# DK_POWER.net
KiCad netlist of a schematic drawn in Altium Designer
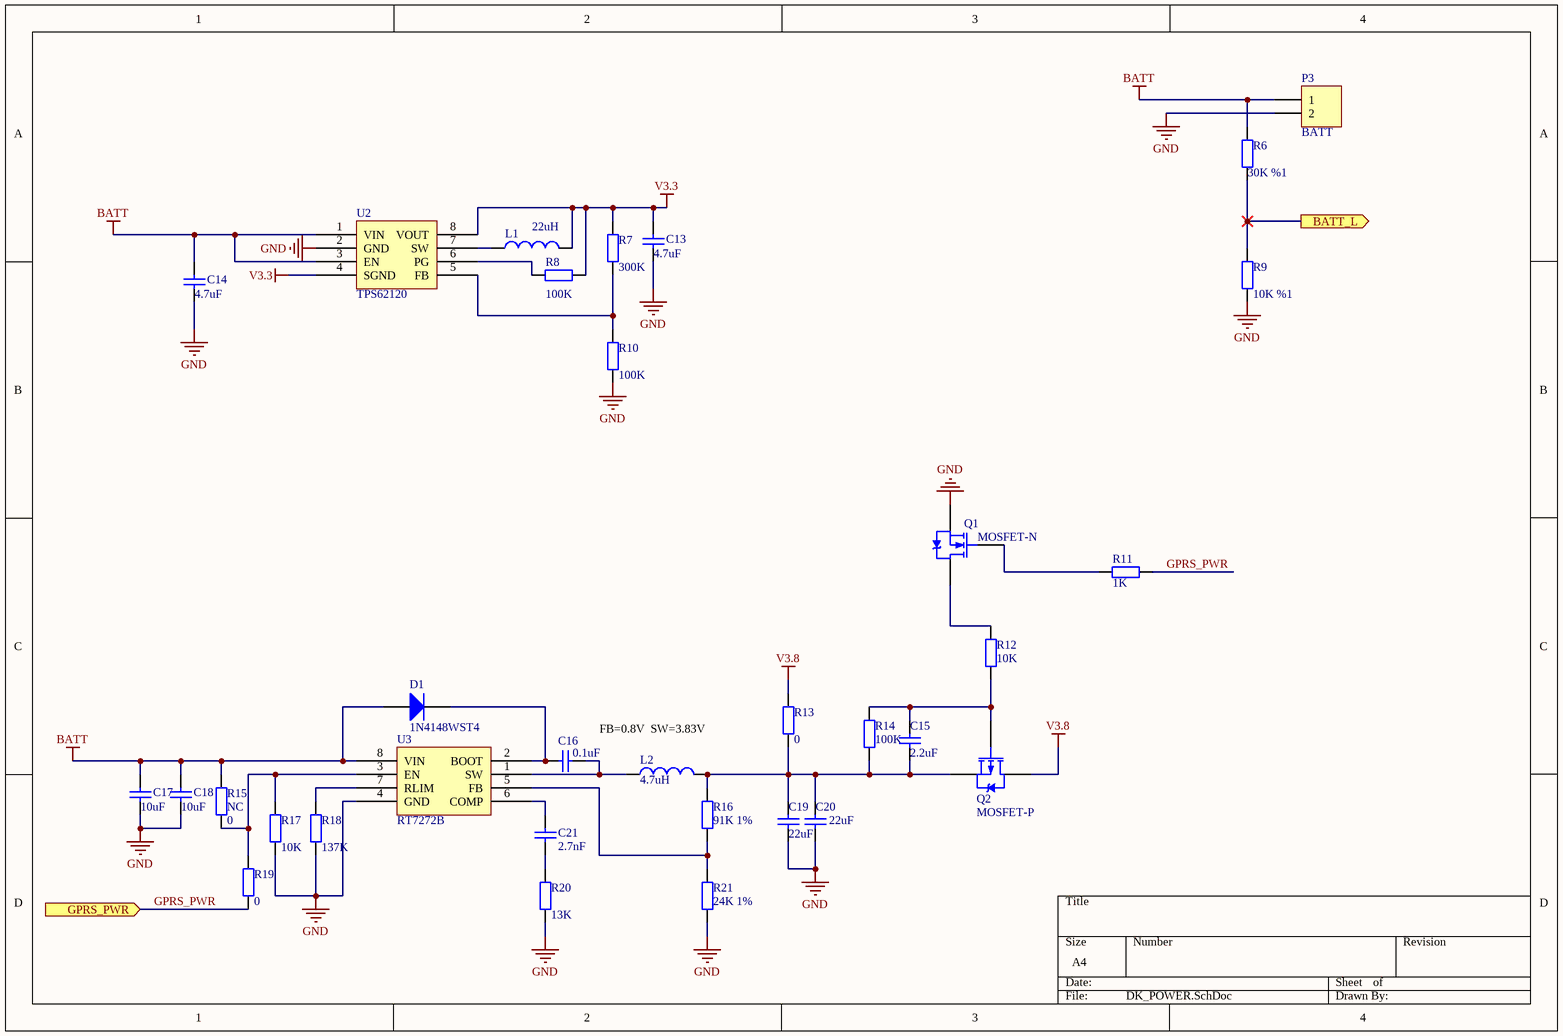
[diagram p0: DK_POWER.SchDoc]

(export (version "E")
  (design (tool "Eeschema 10.0.6"))
  (components
    (comp (ref "C13")
      (value "4.7uF")
      (footprint "0603")
      (description "Capacitor")
      (fields (field (name "Comment") "Cap") (field (name "PUBLISHER") "Altium Limited"))
      (libsource (lib "Miscellaneous Devices") (part "Cap"))
    )
    (comp (ref "C14")
      (value "4.7uF")
      (footprint "0603")
      (description "Capacitor")
      (fields (field (name "Comment") "Cap") (field (name "PUBLISHER") "Altium Limited"))
      (libsource (lib "Miscellaneous Devices") (part "Cap"))
    )
    (comp (ref "C15")
      (value "2.2uF")
      (footprint "0603")
      (description "Capacitor")
      (fields (field (name "Comment") "Cap") (field (name "PUBLISHER") "Altium Limited"))
      (libsource (lib "Miscellaneous Devices") (part "Cap"))
    )
    (comp (ref "C16")
      (value "0.1uF")
      (footprint "0603")
      (description "Capacitor")
      (fields (field (name "Comment") "Cap") (field (name "PUBLISHER") "Altium Limited"))
      (libsource (lib "Miscellaneous Devices") (part "Cap"))
    )
    (comp (ref "C17")
      (value "10uF")
      (footprint "0603")
      (description "Capacitor")
      (fields (field (name "Comment") "Cap") (field (name "PUBLISHER") "Altium Limited"))
      (libsource (lib "Miscellaneous Devices") (part "Cap"))
    )
    (comp (ref "C18")
      (value "10uF")
      (footprint "0603")
      (description "Capacitor")
      (fields (field (name "Comment") "Cap") (field (name "PUBLISHER") "Altium Limited"))
      (libsource (lib "Miscellaneous Devices") (part "Cap"))
    )
    (comp (ref "C19")
      (value "22uF")
      (footprint "0603")
      (description "Capacitor")
      (fields (field (name "Comment") "Cap") (field (name "PUBLISHER") "Altium Limited"))
      (libsource (lib "Miscellaneous Devices") (part "Cap"))
    )
    (comp (ref "C20")
      (value "22uF")
      (footprint "0603")
      (description "Capacitor")
      (fields (field (name "Comment") "Cap") (field (name "PUBLISHER") "Altium Limited"))
      (libsource (lib "Miscellaneous Devices") (part "Cap"))
    )
    (comp (ref "C21")
      (value "2.7nF")
      (footprint "0603")
      (description "Capacitor")
      (fields (field (name "Comment") "Cap") (field (name "PUBLISHER") "Altium Limited"))
      (libsource (lib "Miscellaneous Devices") (part "Cap"))
    )
    (comp (ref "D1")
      (value "1N4148WST4")
      (footprint "SOD-323")
      (description "Default Diode")
      (fields (field (name "PUBLISHER") "Altium Limited"))
      (libsource (lib "Miscellaneous Devices") (part "Diode"))
    )
    (comp (ref "L1")
      (value "22uH")
      (footprint "0630")
      (description "Inductor")
      (fields (field (name "PUBLISHER") "Altium Limited"))
      (libsource (lib "Miscellaneous Devices") (part "Inductor"))
    )
    (comp (ref "L2")
      (value "4.7uH")
      (footprint "0630")
      (description "Inductor")
      (fields (field (name "PUBLISHER") "Altium Limited"))
      (libsource (lib "Miscellaneous Devices") (part "Inductor"))
    )
    (comp (ref "P3")
      (value "BATT")
      (footprint "HEAD2L-0.8")
      (description "Header, 2-Pin")
      (fields (field (name "PUBLISHER") "Altium Limited"))
      (libsource (lib "Miscellaneous Connectors") (part "Header 2"))
    )
    (comp (ref "Q1")
      (value "MOSFET-N")
      (footprint "SOT-23A")
      (description "N-Channel Power MOSFET")
      (fields (field (name "PUBLISHER") "Altium Limited"))
      (libsource (lib "Miscellaneous Devices") (part "NMOS-2"))
    )
    (comp (ref "Q2")
      (value "MOSFET-P")
      (footprint "SOT-23A")
      (description "P-Channel Power MOSFET")
      (fields (field (name "PUBLISHER") "Altium Limited"))
      (libsource (lib "Miscellaneous Devices") (part "PMOS-2"))
    )
    (comp (ref "R6")
      (value "30K %1")
      (footprint "0603")
      (description "Resistor")
      (fields (field (name "Comment") "Res2") (field (name "PUBLISHER") "Altium Limited"))
      (libsource (lib "Miscellaneous Devices") (part "Res2"))
    )
    (comp (ref "R7")
      (value "300K")
      (footprint "0603")
      (description "Resistor")
      (fields (field (name "Comment") "Res2") (field (name "PUBLISHER") "Altium Limited"))
      (libsource (lib "Miscellaneous Devices") (part "Res2"))
    )
    (comp (ref "R8")
      (value "100K")
      (footprint "0603")
      (description "Resistor")
      (fields (field (name "Comment") "Res2") (field (name "PUBLISHER") "Altium Limited"))
      (libsource (lib "") (part "Res2_2"))
    )
    (comp (ref "R9")
      (value "10K %1")
      (footprint "0603")
      (description "Resistor")
      (fields (field (name "Comment") "Res2") (field (name "PUBLISHER") "Altium Limited"))
      (libsource (lib "") (part "Res2_1"))
    )
    (comp (ref "R10")
      (value "100K")
      (footprint "0603")
      (description "Resistor")
      (fields (field (name "Comment") "Res2") (field (name "PUBLISHER") "Altium Limited"))
      (libsource (lib "Miscellaneous Devices") (part "Res2"))
    )
    (comp (ref "R11")
      (value "1K")
      (footprint "0603")
      (description "Resistor")
      (fields (field (name "Comment") "Res2") (field (name "PUBLISHER") "Altium Limited"))
      (libsource (lib "") (part "Res2_2"))
    )
    (comp (ref "R12")
      (value "10K")
      (footprint "0603")
      (description "Resistor")
      (fields (field (name "Comment") "Res2") (field (name "PUBLISHER") "Altium Limited"))
      (libsource (lib "Miscellaneous Devices") (part "Res2"))
    )
    (comp (ref "R13")
      (value "0")
      (footprint "0603")
      (description "Resistor")
      (fields (field (name "Comment") "NC") (field (name "PUBLISHER") "Altium Limited"))
      (libsource (lib "Miscellaneous Devices") (part "Res2"))
    )
    (comp (ref "R14")
      (value "100K")
      (footprint "0603")
      (description "Resistor")
      (fields (field (name "Comment") "Res2") (field (name "PUBLISHER") "Altium Limited"))
      (libsource (lib "Miscellaneous Devices") (part "Res2"))
    )
    (comp (ref "R15")
      (value "NC")
      (footprint "0603")
      (description "Resistor")
      (fields (field (name "ALTIUM_VALUE") "0") (field (name "PUBLISHER") "Altium Limited"))
      (libsource (lib "Miscellaneous Devices") (part "Res2"))
    )
    (comp (ref "R16")
      (value "91K 1%")
      (footprint "0603")
      (description "Resistor")
      (fields (field (name "Comment") "Res2") (field (name "PUBLISHER") "Altium Limited"))
      (libsource (lib "Miscellaneous Devices") (part "Res2"))
    )
    (comp (ref "R17")
      (value "10K")
      (footprint "0603")
      (description "Resistor")
      (fields (field (name "Comment") "Res2") (field (name "PUBLISHER") "Altium Limited"))
      (libsource (lib "Miscellaneous Devices") (part "Res2"))
    )
    (comp (ref "R18")
      (value "137K")
      (footprint "0603")
      (description "Resistor")
      (fields (field (name "Comment") "Res2") (field (name "PUBLISHER") "Altium Limited"))
      (libsource (lib "Miscellaneous Devices") (part "Res2"))
    )
    (comp (ref "R19")
      (value "0")
      (footprint "0603")
      (description "Resistor")
      (fields (field (name "Comment") "Res2") (field (name "PUBLISHER") "Altium Limited"))
      (libsource (lib "Miscellaneous Devices") (part "Res2"))
    )
    (comp (ref "R20")
      (value "13K")
      (footprint "0603")
      (description "Resistor")
      (fields (field (name "Comment") "Res2") (field (name "PUBLISHER") "Altium Limited"))
      (libsource (lib "Miscellaneous Devices") (part "Res2"))
    )
    (comp (ref "R21")
      (value "24K 1%")
      (footprint "0603")
      (description "Resistor")
      (fields (field (name "Comment") "Res2") (field (name "PUBLISHER") "Altium Limited"))
      (libsource (lib "Miscellaneous Devices") (part "Res2"))
    )
    (comp (ref "U2") (value "TPS62120") (footprint "TPS62120") (libsource (lib "TPS62120") (part "TPS62120")))
    (comp (ref "U3") (value "RT7272B") (footprint "RT7272B") (libsource (lib "RT7272B") (part "RT7272B")))
  )
  (nets
    (net (code "1") (name "/BATT_L") (class "Default")
      (node (ref "R6") (pin "1") (pinfunction "1_1") (pintype "passive"))
      (node (ref "R9") (pin "1") (pinfunction "1_1") (pintype "passive"))
    )
    (net (code "2") (name "/GPRS_PWR") (class "Default")
      (node (ref "R11") (pin "2") (pinfunction "2_2") (pintype "passive"))
      (node (ref "R19") (pin "1") (pinfunction "1_1") (pintype "passive"))
    )
    (net (code "3") (name "BATT") (class "Default")
      (node (ref "C14") (pin "2") (pinfunction "2_2") (pintype "passive"))
      (node (ref "C17") (pin "2") (pinfunction "2_2") (pintype "passive"))
      (node (ref "C18") (pin "2") (pinfunction "2_2") (pintype "passive"))
      (node (ref "D1") (pin "1") (pinfunction "A_1") (pintype "passive"))
      (node (ref "P3") (pin "1") (pinfunction "1_1") (pintype "passive"))
      (node (ref "R15") (pin "2") (pinfunction "2_2") (pintype "passive"))
      (node (ref "R6") (pin "2") (pinfunction "2_2") (pintype "passive"))
      (node (ref "U2") (pin "1") (pinfunction "VIN_1") (pintype "passive"))
      (node (ref "U2") (pin "3") (pinfunction "EN_3") (pintype "passive"))
      (node (ref "U3") (pin "8") (pinfunction "VIN_8") (pintype "passive"))
    )
    (net (code "4") (name "GND") (class "Default")
      (node (ref "C13") (pin "1") (pinfunction "1_1") (pintype "passive"))
      (node (ref "C14") (pin "1") (pinfunction "1_1") (pintype "passive"))
      (node (ref "C17") (pin "1") (pinfunction "1_1") (pintype "passive"))
      (node (ref "C18") (pin "1") (pinfunction "1_1") (pintype "passive"))
      (node (ref "C19") (pin "1") (pinfunction "1_1") (pintype "passive"))
      (node (ref "C20") (pin "1") (pinfunction "1_1") (pintype "passive"))
      (node (ref "P3") (pin "2") (pinfunction "2_2") (pintype "passive"))
      (node (ref "Q1") (pin "3") (pinfunction "S_3") (pintype "passive"))
      (node (ref "R10") (pin "1") (pinfunction "1_1") (pintype "passive"))
      (node (ref "R17") (pin "1") (pinfunction "1_1") (pintype "passive"))
      (node (ref "R18") (pin "1") (pinfunction "1_1") (pintype "passive"))
      (node (ref "R20") (pin "1") (pinfunction "1_1") (pintype "passive"))
      (node (ref "R21") (pin "1") (pinfunction "1_1") (pintype "passive"))
      (node (ref "R9") (pin "2") (pinfunction "2_2") (pintype "passive"))
      (node (ref "U2") (pin "2") (pinfunction "GND_2") (pintype "passive"))
      (node (ref "U3") (pin "4") (pinfunction "GND_4") (pintype "passive"))
    )
    (net (code "5") (name "Net-(C21-Pad2)") (class "Default")
      (node (ref "C21") (pin "2") (pinfunction "2_2") (pintype "passive"))
      (node (ref "R20") (pin "2") (pinfunction "2_2") (pintype "passive"))
    )
    (net (code "6") (name "Net-(D1-K)") (class "Default")
      (node (ref "C16") (pin "2") (pinfunction "2_2") (pintype "passive"))
      (node (ref "D1") (pin "2") (pinfunction "K_2") (pintype "passive"))
      (node (ref "U3") (pin "2") (pinfunction "BOOT_2") (pintype "passive"))
    )
    (net (code "7") (name "Net-(Q1-D)") (class "Default")
      (node (ref "Q1") (pin "2") (pinfunction "D_2") (pintype "passive"))
      (node (ref "R12") (pin "2") (pinfunction "2_2") (pintype "passive"))
    )
    (net (code "8") (name "Net-(Q1-G)") (class "Default")
      (node (ref "Q1") (pin "1") (pinfunction "G_1") (pintype "passive"))
      (node (ref "R11") (pin "1") (pinfunction "1_1") (pintype "passive"))
    )
    (net (code "9") (name "Net-(Q2-G)") (class "Default")
      (node (ref "C15") (pin "2") (pinfunction "2_2") (pintype "passive"))
      (node (ref "Q2") (pin "1") (pinfunction "G_1") (pintype "passive"))
      (node (ref "R12") (pin "1") (pinfunction "1_1") (pintype "passive"))
      (node (ref "R14") (pin "2") (pinfunction "2_2") (pintype "passive"))
    )
    (net (code "10") (name "Net-(Q2-S)") (class "Default")
      (node (ref "C15") (pin "1") (pinfunction "1_1") (pintype "passive"))
      (node (ref "C19") (pin "2") (pinfunction "2_2") (pintype "passive"))
      (node (ref "C20") (pin "2") (pinfunction "2_2") (pintype "passive"))
      (node (ref "L2") (pin "2") (pinfunction "2_2") (pintype "passive"))
      (node (ref "Q2") (pin "3") (pinfunction "S_3") (pintype "passive"))
      (node (ref "R13") (pin "1") (pinfunction "1_1") (pintype "passive"))
      (node (ref "R14") (pin "1") (pinfunction "1_1") (pintype "passive"))
      (node (ref "R16") (pin "2") (pinfunction "2_2") (pintype "passive"))
    )
    (net (code "11") (name "Net-(U2-FB)") (class "Default")
      (node (ref "R10") (pin "2") (pinfunction "2_2") (pintype "passive"))
      (node (ref "R7") (pin "1") (pinfunction "1_1") (pintype "passive"))
      (node (ref "U2") (pin "5") (pinfunction "FB_5") (pintype "passive"))
    )
    (net (code "12") (name "Net-(U2-PG)") (class "Default")
      (node (ref "R8") (pin "1") (pinfunction "1_1") (pintype "passive"))
      (node (ref "U2") (pin "6") (pinfunction "PG_6") (pintype "passive"))
    )
    (net (code "13") (name "Net-(U2-SW)") (class "Default")
      (node (ref "L1") (pin "1") (pinfunction "1_1") (pintype "passive"))
      (node (ref "U2") (pin "7") (pinfunction "SW_7") (pintype "passive"))
    )
    (net (code "14") (name "Net-(U3-COMP)") (class "Default")
      (node (ref "C21") (pin "1") (pinfunction "1_1") (pintype "passive"))
      (node (ref "U3") (pin "6") (pinfunction "COMP_6") (pintype "passive"))
    )
    (net (code "15") (name "Net-(U3-EN)") (class "Default")
      (node (ref "R15") (pin "1") (pinfunction "1_1") (pintype "passive"))
      (node (ref "R17") (pin "2") (pinfunction "2_2") (pintype "passive"))
      (node (ref "R19") (pin "2") (pinfunction "2_2") (pintype "passive"))
      (node (ref "U3") (pin "3") (pinfunction "EN_3") (pintype "passive"))
    )
    (net (code "16") (name "Net-(U3-FB)") (class "Default")
      (node (ref "R16") (pin "1") (pinfunction "1_1") (pintype "passive"))
      (node (ref "R21") (pin "2") (pinfunction "2_2") (pintype "passive"))
      (node (ref "U3") (pin "5") (pinfunction "FB_5") (pintype "passive"))
    )
    (net (code "17") (name "Net-(U3-RLIM)") (class "Default")
      (node (ref "R18") (pin "2") (pinfunction "2_2") (pintype "passive"))
      (node (ref "U3") (pin "7") (pinfunction "RLIM_7") (pintype "passive"))
    )
    (net (code "18") (name "Net-(U3-SW)") (class "Default")
      (node (ref "C16") (pin "1") (pinfunction "1_1") (pintype "passive"))
      (node (ref "L2") (pin "1") (pinfunction "1_1") (pintype "passive"))
      (node (ref "U3") (pin "1") (pinfunction "SW_1") (pintype "passive"))
    )
    (net (code "19") (name "V3.3") (class "Default")
      (node (ref "C13") (pin "2") (pinfunction "2_2") (pintype "passive"))
      (node (ref "L1") (pin "2") (pinfunction "2_2") (pintype "passive"))
      (node (ref "R7") (pin "2") (pinfunction "2_2") (pintype "passive"))
      (node (ref "R8") (pin "2") (pinfunction "2_2") (pintype "passive"))
      (node (ref "U2") (pin "4") (pinfunction "SGND_4") (pintype "passive"))
      (node (ref "U2") (pin "8") (pinfunction "VOUT_8") (pintype "passive"))
    )
    (net (code "20") (name "V3.8") (class "Default")
      (node (ref "Q2") (pin "2") (pinfunction "D_2") (pintype "passive"))
      (node (ref "R13") (pin "2") (pinfunction "2_2") (pintype "passive"))
    )
  )
)
